# jBoard2.net
KiCad netlist of a schematic drawn in EAGLE
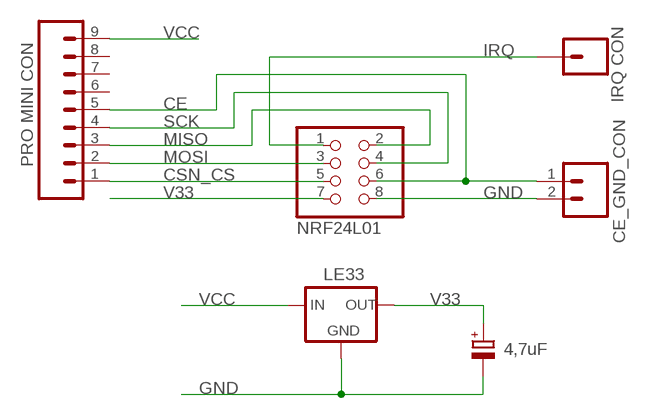
[diagram p0: schematic, sheet 1]

(export (version "E")
  (design (tool "Eeschema 10.0.6"))
  (components
    (comp (ref "C3")
      (value "4,7uF")
      (footprint "eagle-import:E2-5")
      (libsource (lib "eagle-import") (part "CPOL-EUE2-5"))
    )
    (comp (ref "IC1")
      (value "LE33")
      (footprint "eagle-import:78LXX")
      (libsource (lib "eagle-import") (part "78LXX"))
    )
    (comp (ref "J1")
      (value "PRO MINI CON")
      (footprint "eagle-import:1X09")
      (libsource (lib "eagle-import") (part "M09"))
    )
    (comp (ref "J2")
      (value "IRQ CON")
      (footprint "eagle-import:1X01")
      (libsource (lib "eagle-import") (part "CONN_01"))
    )
    (comp (ref "J3")
      (value "CE_GND_CON")
      (footprint "eagle-import:1X02")
      (libsource (lib "eagle-import") (part "CONN_02"))
    )
    (comp (ref "JP2")
      (value "NRF24L01")
      (footprint "eagle-import:2X04")
      (libsource (lib "eagle-import") (part "PINHD-2X4"))
    )
  )
  (nets
    (net (code "1") (name "/CE") (class "Default")
      (node (ref "J1") (pin "5") (pinfunction "5_5") (pintype "passive"))
      (node (ref "J3") (pin "1") (pinfunction "1_1") (pintype "passive"))
      (node (ref "JP2") (pin "6") (pinfunction "6_6") (pintype "passive"))
    )
    (net (code "2") (name "/CSN_CS") (class "Default")
      (node (ref "J1") (pin "1") (pinfunction "1_1") (pintype "passive"))
      (node (ref "JP2") (pin "5") (pinfunction "5_5") (pintype "passive"))
    )
    (net (code "3") (name "/GND") (class "Default")
      (node (ref "C3") (pin "-") (pinfunction "-_-") (pintype "passive"))
      (node (ref "IC1") (pin "GND") (pinfunction "GND_GND") (pintype "input"))
      (node (ref "J3") (pin "2") (pinfunction "2_2") (pintype "passive"))
      (node (ref "JP2") (pin "8") (pinfunction "8_8") (pintype "passive"))
    )
    (net (code "4") (name "/IRQ") (class "Default")
      (node (ref "J2") (pin "1") (pinfunction "1_1") (pintype "passive"))
      (node (ref "JP2") (pin "1") (pinfunction "1_1") (pintype "passive"))
    )
    (net (code "5") (name "/MISO") (class "Default")
      (node (ref "J1") (pin "3") (pinfunction "3_3") (pintype "passive"))
      (node (ref "JP2") (pin "2") (pinfunction "2_2") (pintype "passive"))
    )
    (net (code "6") (name "/MOSI") (class "Default")
      (node (ref "J1") (pin "2") (pinfunction "2_2") (pintype "passive"))
      (node (ref "JP2") (pin "3") (pinfunction "3_3") (pintype "passive"))
    )
    (net (code "7") (name "/SCK") (class "Default")
      (node (ref "J1") (pin "4") (pinfunction "4_4") (pintype "passive"))
      (node (ref "JP2") (pin "4") (pinfunction "4_4") (pintype "passive"))
    )
    (net (code "8") (name "/V33") (class "Default")
      (node (ref "C3") (pin "+") (pinfunction "+_+") (pintype "passive"))
      (node (ref "IC1") (pin "OUT") (pinfunction "OUT_OUT") (pintype "passive"))
      (node (ref "JP2") (pin "7") (pinfunction "7_7") (pintype "passive"))
    )
    (net (code "9") (name "/VCC") (class "Default")
      (node (ref "IC1") (pin "IN") (pinfunction "IN_IN") (pintype "input"))
      (node (ref "J1") (pin "9") (pinfunction "9_9") (pintype "passive"))
    )
    (net (code "10") (name "unconnected-(J1-Pad6)") (class "Default")
      (node (ref "J1") (pin "6") (pinfunction "6_6") (pintype "passive"))
    )
    (net (code "11") (name "unconnected-(J1-Pad7)") (class "Default")
      (node (ref "J1") (pin "7") (pinfunction "7_7") (pintype "passive"))
    )
    (net (code "12") (name "unconnected-(J1-Pad8)") (class "Default")
      (node (ref "J1") (pin "8") (pinfunction "8_8") (pintype "passive"))
    )
  )
)
